# MED_BOX.net
KiCad netlist of a schematic drawn in Altium Designer
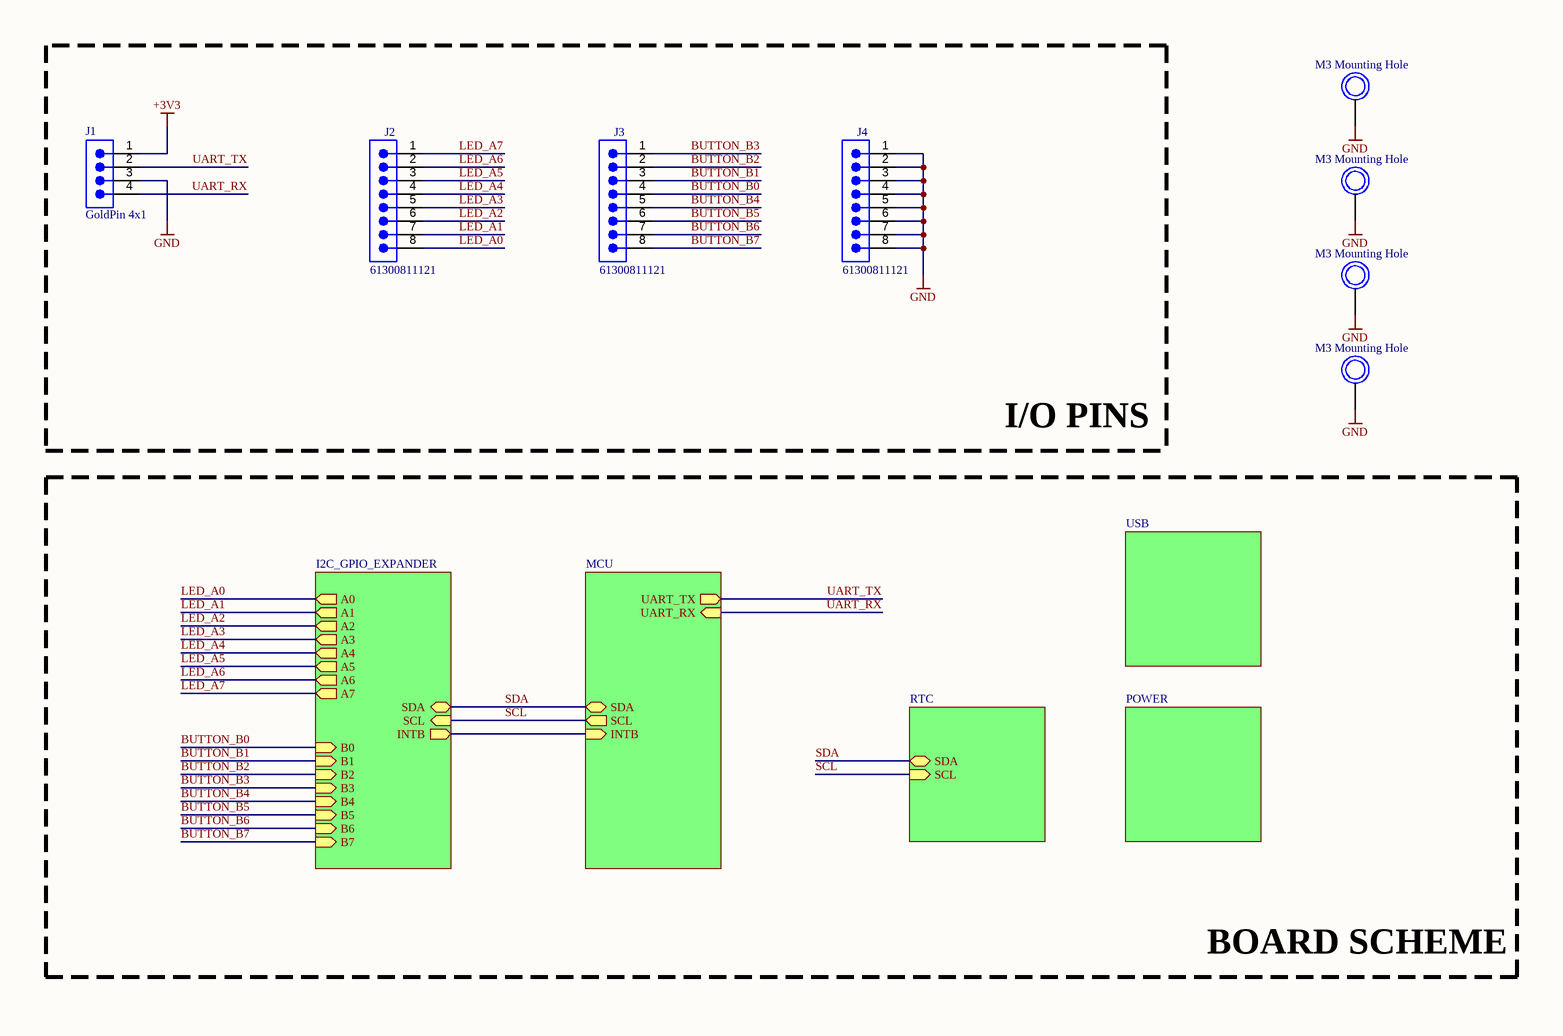
[diagram p0: MED_BOX.SchDoc]

(export (version "E")
  (design (tool "Eeschema 10.0.6"))
  (components
    (comp (ref "J1")
      (value "GoldPin 4x1")
      (footprint "SMTC-TSW-104-08-X-S")
      (description "TSW - Samtec 2.54mm Pin Header 13.46mm Overall Pin Length 5.08mm Tail (08) (mcv)(TO22)")
      (fields (field (name "MANUFACTURER") "Molex"))
      (libsource (lib "PolSl Racing - Electrical") (part "GoldPin 4x1"))
    )
    (comp (ref "J2")
      (value "61300811121")
      (footprint "61300811121")
      (description "THT Vertical Pin Header WR-PHD, Pitch 2.54 mm, Single Row, 8 pins")
      (libsource (lib "Altium Content Vault") (part "Header_Male_1R_08P"))
    )
    (comp (ref "J3")
      (value "61300811121")
      (footprint "61300811121")
      (description "THT Vertical Pin Header WR-PHD, Pitch 2.54 mm, Single Row, 8 pins")
      (libsource (lib "Altium Content Vault") (part "Header_Male_1R_08P"))
    )
    (comp (ref "J4")
      (value "61300811121")
      (footprint "61300811121")
      (description "THT Vertical Pin Header WR-PHD, Pitch 2.54 mm, Single Row, 8 pins")
      (libsource (lib "Altium Content Vault") (part "Header_Male_1R_08P"))
    )
    (comp (ref "MH1")
      (value "M3 Mounting Hole")
      (footprint "Copy of M4 Mounting Hole")
      (fields (field (name "MANUFACTURER") "Molex"))
      (libsource (lib "PolSl Racing - Electrical") (part "Mounting Hole"))
    )
    (comp (ref "MH2")
      (value "M3 Mounting Hole")
      (footprint "Copy of M4 Mounting Hole")
      (fields (field (name "MANUFACTURER") "Molex"))
      (libsource (lib "PolSl Racing - Electrical") (part "Mounting Hole"))
    )
    (comp (ref "MH3")
      (value "M3 Mounting Hole")
      (footprint "Copy of M4 Mounting Hole")
      (fields (field (name "MANUFACTURER") "Molex"))
      (libsource (lib "PolSl Racing - Electrical") (part "Mounting Hole"))
    )
    (comp (ref "MH4")
      (value "M3 Mounting Hole")
      (footprint "Copy of M4 Mounting Hole")
      (fields (field (name "MANUFACTURER") "Molex"))
      (libsource (lib "PolSl Racing - Electrical") (part "Mounting Hole"))
    )
  )
  (nets
    (net (code "1") (name "+3V3") (class "Default")
      (node (ref "J1") (pin "1") (pinfunction "1_1") (pintype "passive"))
    )
    (net (code "2") (name "/BUTTON_B0") (class "Default")
      (node (ref "J3") (pin "4") (pinfunction "4_4") (pintype "passive"))
    )
    (net (code "3") (name "/BUTTON_B1") (class "Default")
      (node (ref "J3") (pin "3") (pinfunction "3_3") (pintype "passive"))
    )
    (net (code "4") (name "/BUTTON_B2") (class "Default")
      (node (ref "J3") (pin "2") (pinfunction "2_2") (pintype "passive"))
    )
    (net (code "5") (name "/BUTTON_B3") (class "Default")
      (node (ref "J3") (pin "1") (pinfunction "1_1") (pintype "passive"))
    )
    (net (code "6") (name "/BUTTON_B4") (class "Default")
      (node (ref "J3") (pin "5") (pinfunction "5_5") (pintype "passive"))
    )
    (net (code "7") (name "/BUTTON_B5") (class "Default")
      (node (ref "J3") (pin "6") (pinfunction "6_6") (pintype "passive"))
    )
    (net (code "8") (name "/BUTTON_B6") (class "Default")
      (node (ref "J3") (pin "7") (pinfunction "7_7") (pintype "passive"))
    )
    (net (code "9") (name "/BUTTON_B7") (class "Default")
      (node (ref "J3") (pin "8") (pinfunction "8_8") (pintype "passive"))
    )
    (net (code "11") (name "/LED_A0") (class "Default")
      (node (ref "J2") (pin "8") (pinfunction "8_8") (pintype "passive"))
    )
    (net (code "12") (name "/LED_A1") (class "Default")
      (node (ref "J2") (pin "7") (pinfunction "7_7") (pintype "passive"))
    )
    (net (code "13") (name "/LED_A2") (class "Default")
      (node (ref "J2") (pin "6") (pinfunction "6_6") (pintype "passive"))
    )
    (net (code "14") (name "/LED_A3") (class "Default")
      (node (ref "J2") (pin "5") (pinfunction "5_5") (pintype "passive"))
    )
    (net (code "15") (name "/LED_A4") (class "Default")
      (node (ref "J2") (pin "4") (pinfunction "4_4") (pintype "passive"))
    )
    (net (code "16") (name "/LED_A5") (class "Default")
      (node (ref "J2") (pin "3") (pinfunction "3_3") (pintype "passive"))
    )
    (net (code "17") (name "/LED_A6") (class "Default")
      (node (ref "J2") (pin "2") (pinfunction "2_2") (pintype "passive"))
    )
    (net (code "18") (name "/LED_A7") (class "Default")
      (node (ref "J2") (pin "1") (pinfunction "1_1") (pintype "passive"))
    )
    (net (code "21") (name "/UART_RX") (class "Default")
      (node (ref "J1") (pin "4") (pinfunction "4_4") (pintype "passive"))
    )
    (net (code "22") (name "/UART_TX") (class "Default")
      (node (ref "J1") (pin "2") (pinfunction "2_2") (pintype "passive"))
    )
    (net (code "23") (name "GND") (class "Default")
      (node (ref "J1") (pin "3") (pinfunction "3_3") (pintype "passive"))
      (node (ref "J4") (pin "1") (pinfunction "1_1") (pintype "passive"))
      (node (ref "J4") (pin "2") (pinfunction "2_2") (pintype "passive"))
      (node (ref "J4") (pin "3") (pinfunction "3_3") (pintype "passive"))
      (node (ref "J4") (pin "4") (pinfunction "4_4") (pintype "passive"))
      (node (ref "J4") (pin "5") (pinfunction "5_5") (pintype "passive"))
      (node (ref "J4") (pin "6") (pinfunction "6_6") (pintype "passive"))
      (node (ref "J4") (pin "7") (pinfunction "7_7") (pintype "passive"))
      (node (ref "J4") (pin "8") (pinfunction "8_8") (pintype "passive"))
      (node (ref "MH1") (pin "1") (pinfunction "1_1") (pintype "passive"))
      (node (ref "MH2") (pin "1") (pinfunction "1_1") (pintype "passive"))
      (node (ref "MH3") (pin "1") (pinfunction "1_1") (pintype "passive"))
      (node (ref "MH4") (pin "1") (pinfunction "1_1") (pintype "passive"))
    )
  )
)
